# XT-03_Bit_Reducer_CEMC.net
KiCad netlist of a schematic drawn in EAGLE
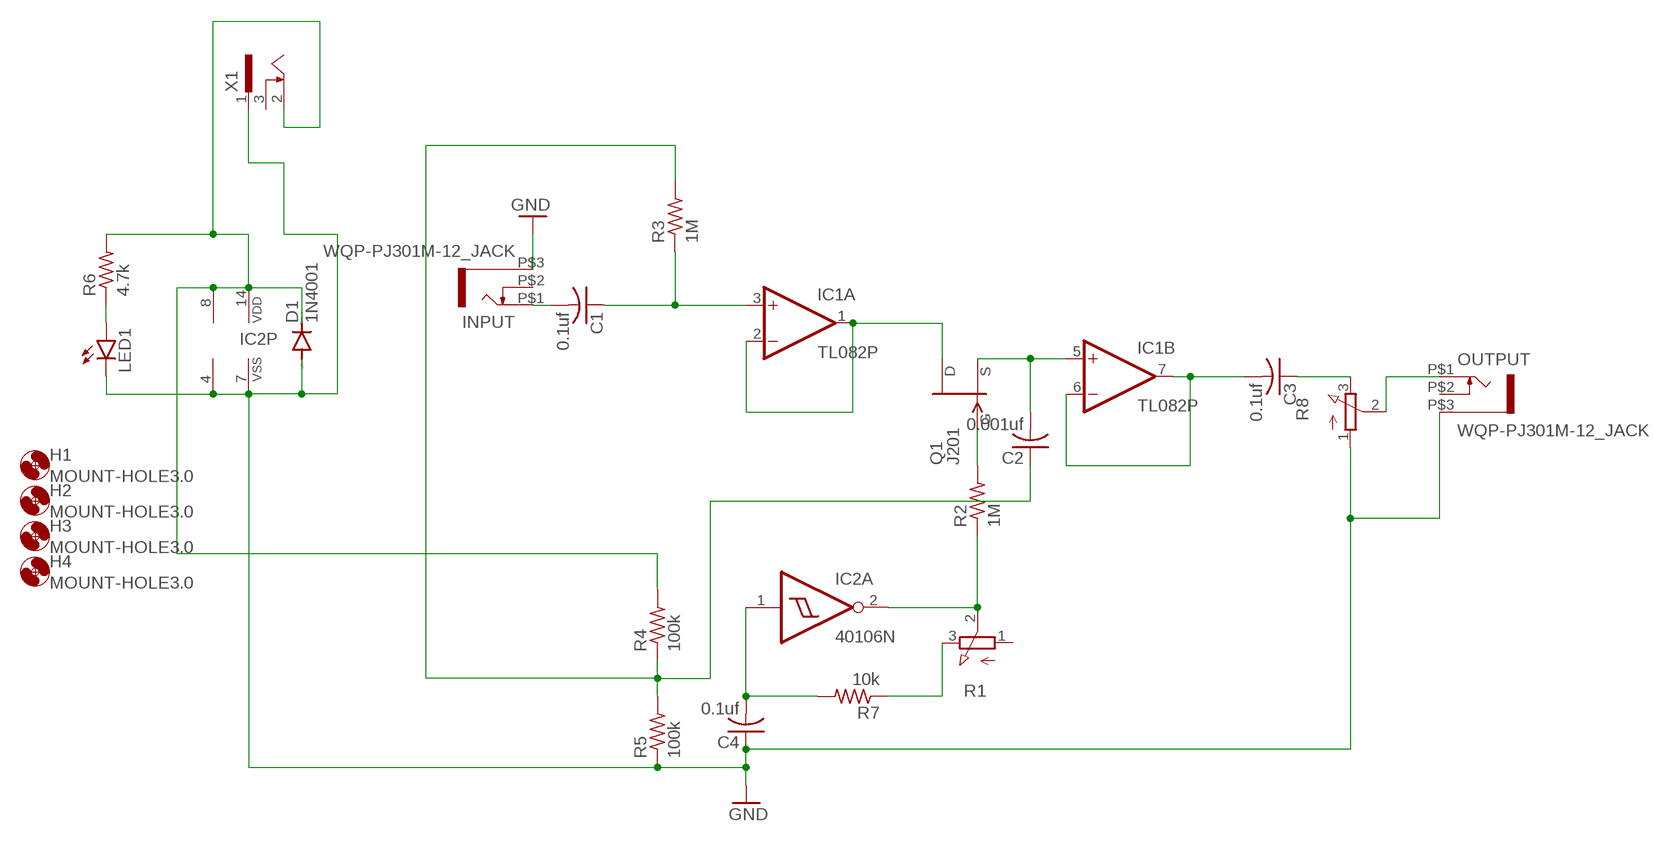
[diagram p0: schematic, sheet 1]

(export (version "E")
  (design (tool "Eeschema 10.0.6"))
  (components
    (comp (ref "C1")
      (value "0.1uf")
      (footprint "eagle-import:C050-025X075")
      (libsource (lib "eagle-import") (part "C-US050-025X075"))
    )
    (comp (ref "C2")
      (value "0.001uf")
      (footprint "eagle-import:C050-025X075")
      (libsource (lib "eagle-import") (part "C-US050-025X075"))
    )
    (comp (ref "C3")
      (value "0.1uf")
      (footprint "eagle-import:C050-025X075")
      (libsource (lib "eagle-import") (part "C-US050-025X075"))
    )
    (comp (ref "C4")
      (value "0.1uf")
      (footprint "eagle-import:C050-025X075")
      (libsource (lib "eagle-import") (part "C-US050-025X075"))
    )
    (comp (ref "D1")
      (value "1N4001")
      (footprint "eagle-import:DO41-10")
      (libsource (lib "eagle-import") (part "1N4004"))
    )
    (comp (ref "H1")
      (value "MOUNT-HOLE3.0")
      (footprint "eagle-import:3,0")
      (libsource (lib "eagle-import") (part "MOUNT-HOLE3.0"))
    )
    (comp (ref "H2")
      (value "MOUNT-HOLE3.0")
      (footprint "eagle-import:3,0")
      (libsource (lib "eagle-import") (part "MOUNT-HOLE3.0"))
    )
    (comp (ref "H3")
      (value "MOUNT-HOLE3.0")
      (footprint "eagle-import:3,0")
      (libsource (lib "eagle-import") (part "MOUNT-HOLE3.0"))
    )
    (comp (ref "H4")
      (value "MOUNT-HOLE3.0")
      (footprint "eagle-import:3,0")
      (libsource (lib "eagle-import") (part "MOUNT-HOLE3.0"))
    )
    (comp (ref "IC1")
      (value "TL082P")
      (footprint "eagle-import:DIL08")
      (libsource (lib "eagle-import") (part "TL082P"))
    )
    (comp (ref "IC2")
      (value "40106N")
      (footprint "eagle-import:DIL14")
      (libsource (lib "eagle-import") (part "40106N"))
    )
    (comp (ref "INPUT")
      (value "WQP-PJ301M-12_JACK")
      (footprint "eagle-import:WQP-PJ301M-12_JACK")
      (libsource (lib "eagle-import") (part "WQP-PJ301M-12_JACK"))
    )
    (comp (ref "LED1")
      (value "LED3MM")
      (footprint "eagle-import:LED3MM")
      (libsource (lib "eagle-import") (part "LED3MM"))
    )
    (comp (ref "OUTPUT")
      (value "WQP-PJ301M-12_JACK")
      (footprint "eagle-import:WQP-PJ301M-12_JACK")
      (libsource (lib "eagle-import") (part "WQP-PJ301M-12_JACK"))
    )
    (comp (ref "Q1")
      (value "J201")
      (footprint "eagle-import:TO92")
      (libsource (lib "eagle-import") (part "?20J1"))
    )
    (comp (ref "R1")
      (value "EVUF2L")
      (footprint "eagle-import:EVUFXL")
      (libsource (lib "eagle-import") (part "EVULF2"))
    )
    (comp (ref "R2")
      (value "1M")
      (footprint "eagle-import:0207_7")
      (libsource (lib "eagle-import") (part "R-US_0207/7"))
    )
    (comp (ref "R3")
      (value "1M")
      (footprint "eagle-import:0207_7")
      (libsource (lib "eagle-import") (part "R-US_0207/7"))
    )
    (comp (ref "R4")
      (value "100k")
      (footprint "eagle-import:0207_7")
      (libsource (lib "eagle-import") (part "R-US_0207/7"))
    )
    (comp (ref "R5")
      (value "100k")
      (footprint "eagle-import:0207_7")
      (libsource (lib "eagle-import") (part "R-US_0207/7"))
    )
    (comp (ref "R6")
      (value "4.7k")
      (footprint "eagle-import:0207_7")
      (libsource (lib "eagle-import") (part "R-US_0207/7"))
    )
    (comp (ref "R7")
      (value "10k")
      (footprint "eagle-import:0207_7")
      (libsource (lib "eagle-import") (part "R-US_0207/7"))
    )
    (comp (ref "R8")
      (value "EVUF2L")
      (footprint "eagle-import:EVUFXL")
      (libsource (lib "eagle-import") (part "EVULF2"))
    )
    (comp (ref "X1")
      (value "SCD-014A")
      (footprint "eagle-import:SCD-014-A")
      (libsource (lib "eagle-import") (part "SCD-014A"))
    )
  )
  (nets
    (net (code "1") (name "GND") (class "Default")
      (node (ref "C4") (pin "1") (pinfunction "1_1") (pintype "passive"))
      (node (ref "D1") (pin "A") (pinfunction "A_A") (pintype "passive"))
      (node (ref "IC1") (pin "4") (pinfunction "V-_4") (pintype "power_in"))
      (node (ref "IC2") (pin "7") (pinfunction "VSS_7") (pintype "power_in"))
      (node (ref "INPUT") (pin "P$3") (pinfunction "1_P$3") (pintype "passive"))
      (node (ref "LED1") (pin "K") (pinfunction "C_K") (pintype "passive"))
      (node (ref "OUTPUT") (pin "P$3") (pinfunction "1_P$3") (pintype "passive"))
      (node (ref "R5") (pin "1") (pinfunction "1_1") (pintype "passive"))
      (node (ref "R8") (pin "1") (pinfunction "A_1") (pintype "passive"))
      (node (ref "X1") (pin "1") (pinfunction "1_1") (pintype "passive"))
    )
    (net (code "2") (name "Net-(C2-Pad1)") (class "Default")
      (node (ref "C2") (pin "1") (pinfunction "1_1") (pintype "passive"))
      (node (ref "R3") (pin "2") (pinfunction "2_2") (pintype "passive"))
      (node (ref "R4") (pin "1") (pinfunction "1_1") (pintype "passive"))
      (node (ref "R5") (pin "2") (pinfunction "2_2") (pintype "passive"))
    )
    (net (code "3") (name "Net-(IC1A-+IN)") (class "Default")
      (node (ref "C1") (pin "1") (pinfunction "1_1") (pintype "passive"))
      (node (ref "IC1") (pin "3") (pinfunction "+IN_3") (pintype "input"))
      (node (ref "R3") (pin "1") (pinfunction "1_1") (pintype "passive"))
    )
    (net (code "4") (name "Net-(IC1A--IN)") (class "Default")
      (node (ref "IC1") (pin "1") (pinfunction "OUT_1") (pintype "output"))
      (node (ref "IC1") (pin "2") (pinfunction "-IN_2") (pintype "input"))
      (node (ref "Q1") (pin "3") (pinfunction "D_3") (pintype "passive"))
    )
    (net (code "5") (name "Net-(IC1B-+IN)") (class "Default")
      (node (ref "C2") (pin "2") (pinfunction "2_2") (pintype "passive"))
      (node (ref "IC1") (pin "5") (pinfunction "+IN_5") (pintype "input"))
      (node (ref "Q1") (pin "2") (pinfunction "S_2") (pintype "passive"))
    )
    (net (code "6") (name "Net-(IC1B--IN)") (class "Default")
      (node (ref "C3") (pin "2") (pinfunction "2_2") (pintype "passive"))
      (node (ref "IC1") (pin "6") (pinfunction "-IN_6") (pintype "input"))
      (node (ref "IC1") (pin "7") (pinfunction "OUT_7") (pintype "output"))
    )
    (net (code "7") (name "Net-(IC1C-V+)") (class "Default")
      (node (ref "D1") (pin "C") (pinfunction "C_C") (pintype "passive"))
      (node (ref "IC1") (pin "8") (pinfunction "V+_8") (pintype "power_in"))
      (node (ref "IC2") (pin "14") (pinfunction "VDD_14") (pintype "power_in"))
      (node (ref "R4") (pin "2") (pinfunction "2_2") (pintype "passive"))
      (node (ref "R6") (pin "2") (pinfunction "2_2") (pintype "passive"))
      (node (ref "X1") (pin "2") (pinfunction "2_2") (pintype "passive"))
    )
    (net (code "8") (name "Net-(IC2A-I)") (class "Default")
      (node (ref "C4") (pin "2") (pinfunction "2_2") (pintype "passive"))
      (node (ref "IC2") (pin "1") (pinfunction "I_1") (pintype "input"))
      (node (ref "R7") (pin "2") (pinfunction "2_2") (pintype "passive"))
    )
    (net (code "9") (name "Net-(IC2A-O)") (class "Default")
      (node (ref "IC2") (pin "2") (pinfunction "O_2") (pintype "output"))
      (node (ref "R1") (pin "2") (pinfunction "S_2") (pintype "passive"))
      (node (ref "R2") (pin "1") (pinfunction "1_1") (pintype "passive"))
    )
    (net (code "10") (name "Net-(INPUT-2)") (class "Default")
      (node (ref "C1") (pin "2") (pinfunction "2_2") (pintype "passive"))
      (node (ref "INPUT") (pin "P$1") (pinfunction "2_P$1") (pintype "passive"))
    )
    (net (code "11") (name "Net-(LED1-PadA)") (class "Default")
      (node (ref "LED1") (pin "A") (pinfunction "A_A") (pintype "passive"))
      (node (ref "R6") (pin "1") (pinfunction "1_1") (pintype "passive"))
    )
    (net (code "12") (name "Net-(OUTPUT-2)") (class "Default")
      (node (ref "OUTPUT") (pin "P$1") (pinfunction "2_P$1") (pintype "passive"))
      (node (ref "R8") (pin "2") (pinfunction "S_2") (pintype "passive"))
    )
    (net (code "13") (name "Net-(Q1-G)") (class "Default")
      (node (ref "Q1") (pin "1") (pinfunction "G_1") (pintype "passive"))
      (node (ref "R2") (pin "2") (pinfunction "2_2") (pintype "passive"))
    )
    (net (code "14") (name "Net-(R1-E)") (class "Default")
      (node (ref "R1") (pin "3") (pinfunction "E_3") (pintype "passive"))
      (node (ref "R7") (pin "1") (pinfunction "1_1") (pintype "passive"))
    )
    (net (code "15") (name "Net-(R8-E)") (class "Default")
      (node (ref "C3") (pin "1") (pinfunction "1_1") (pintype "passive"))
      (node (ref "R8") (pin "3") (pinfunction "E_3") (pintype "passive"))
    )
    (net (code "16") (name "unconnected-(INPUT-3-PadP$2)") (class "Default")
      (node (ref "INPUT") (pin "P$2") (pinfunction "3_P$2") (pintype "passive"))
    )
    (net (code "17") (name "unconnected-(OUTPUT-3-PadP$2)") (class "Default")
      (node (ref "OUTPUT") (pin "P$2") (pinfunction "3_P$2") (pintype "passive"))
    )
    (net (code "18") (name "unconnected-(R1-A-Pad1)") (class "Default")
      (node (ref "R1") (pin "1") (pinfunction "A_1") (pintype "passive"))
    )
    (net (code "19") (name "unconnected-(X1-Pad3)") (class "Default")
      (node (ref "X1") (pin "3") (pinfunction "3_3") (pintype "passive"))
    )
  )
)
